# MainBoard.net
KiCad netlist of a schematic drawn in Altium Designer
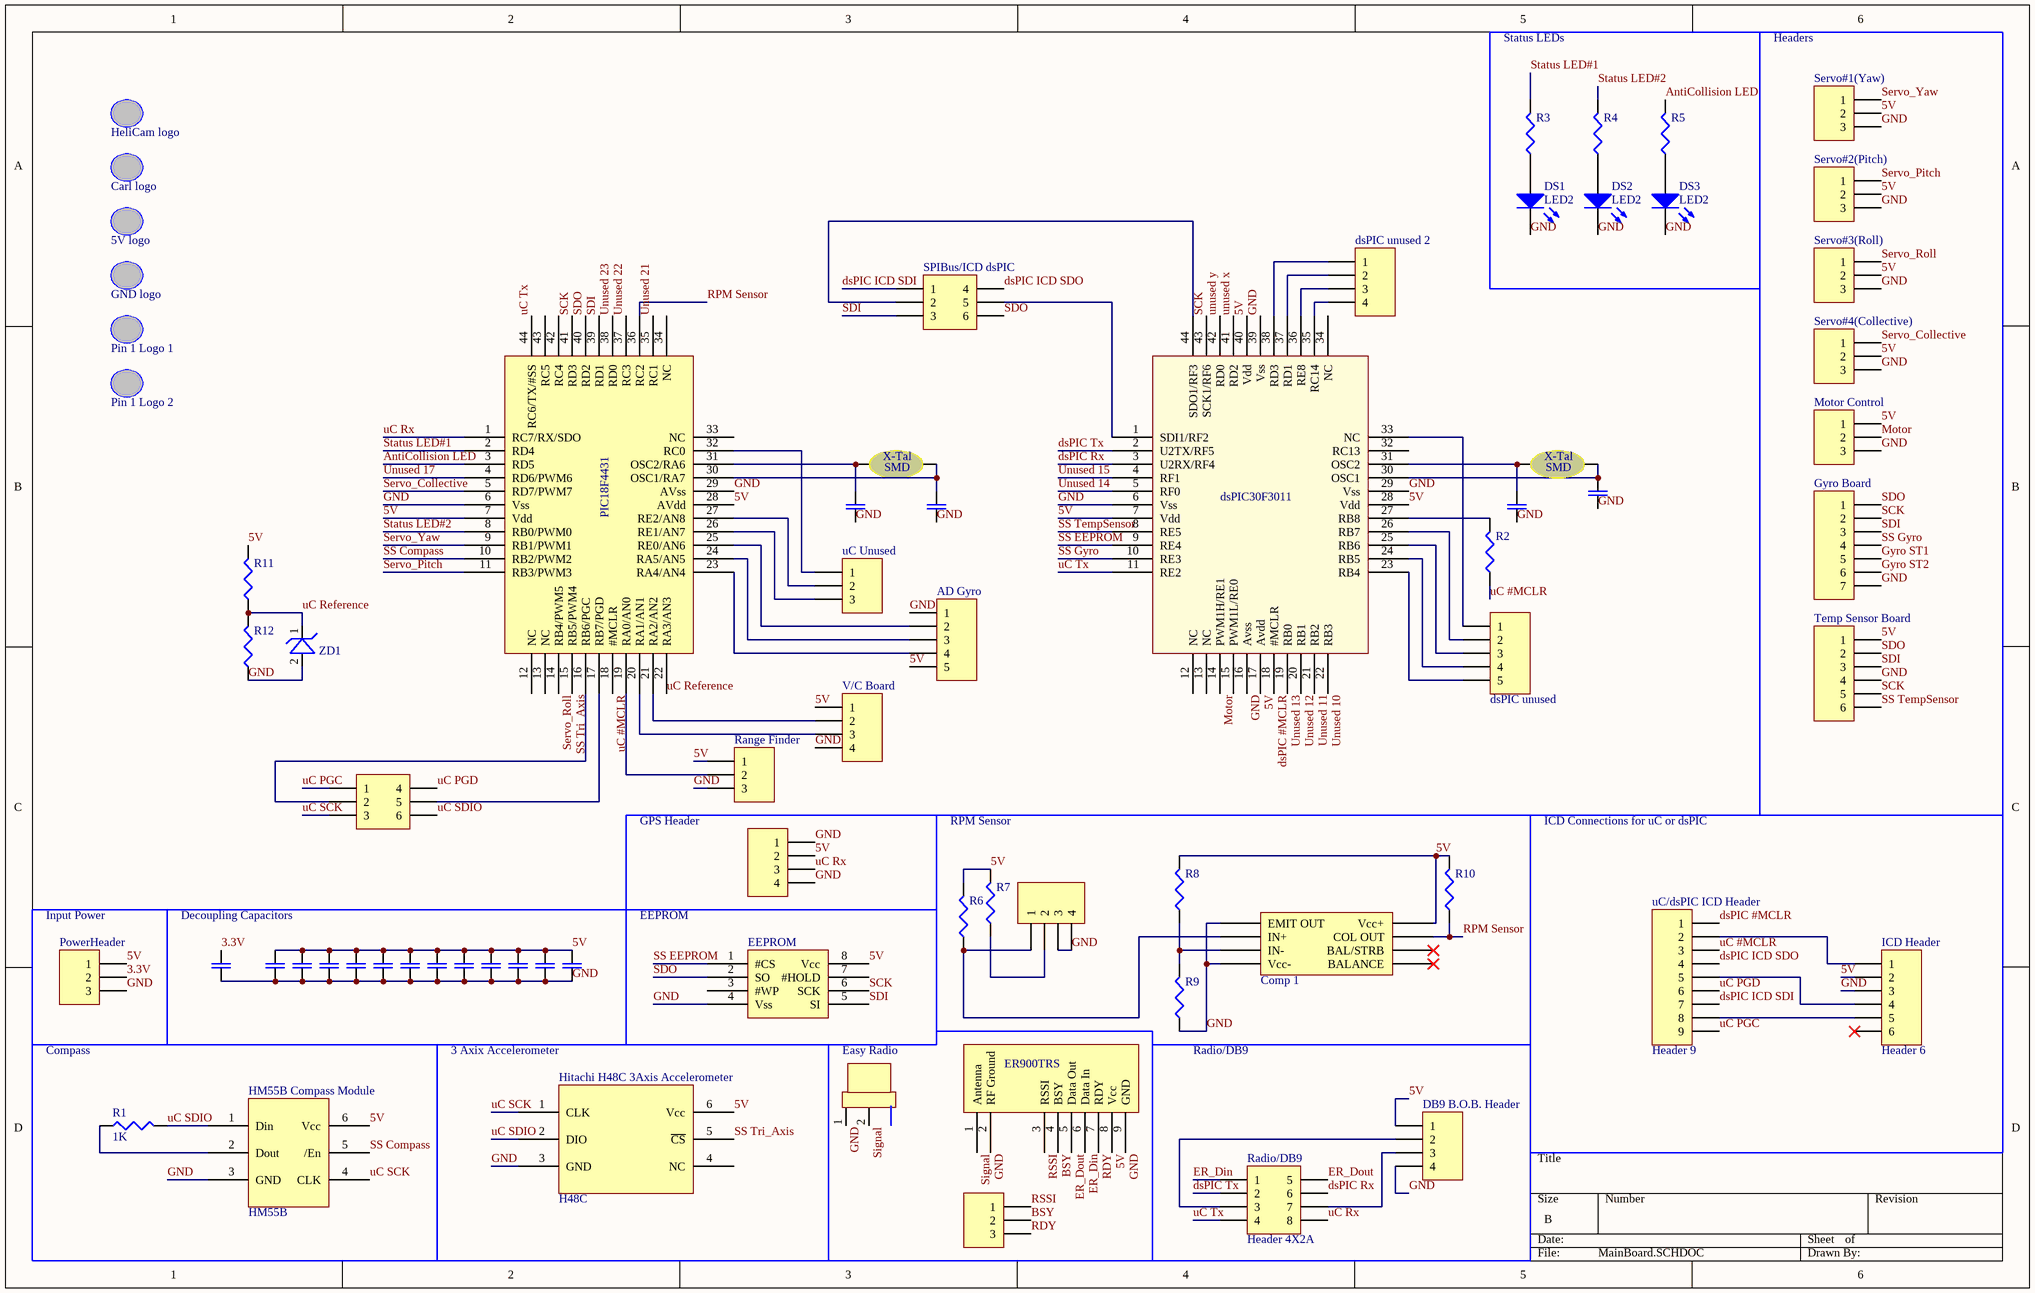
[diagram p0: MainBoard.SCHDOC]

(export (version "E")
  (design (tool "Eeschema 10.0.6"))
  (components
    (comp (ref "5V logo") (value "logo") (footprint "5V logo") (libsource (lib "MyParts") (part "logo")))
    (comp (ref "AD Gyro")
      (value "Header 5")
      (footprint "HDR1X5")
      (description "Header, 5-Pin")
      (fields (field (name "PUBLISHER") "Altium Limited"))
      (libsource (lib "Miscellaneous Connectors") (part "Header 5"))
    )
    (comp (ref "Antenna Connector 1")
      (value "Antenna Connector")
      (footprint "Antenna Connector")
      (libsource (lib "MyParts") (part "Antenna Connector"))
    )
    (comp (ref "Carl logo") (value "logo") (footprint "Carl Logo") (libsource (lib "MyParts") (part "logo")))
    (comp (ref "Comp 1")
      (value "Comparator")
      (footprint "8-Pin DIP")
      (libsource (lib "MyParts") (part "LP311P"))
    )
    (comp (ref "DB9 B.O.B. Header")
      (value "DB9 Break Out Board Header")
      (footprint "HDR1X4")
      (description "Header, 4-Pin")
      (fields (field (name "PUBLISHER") "Altium Limited"))
      (libsource (lib "Miscellaneous Connectors") (part "Header 4"))
    )
    (comp (ref "DS1")
      (value "LED2")
      (footprint "DSO-F2/D6.1")
      (description "Typical RED, GREEN, YELLOW, AMBER GaAs LED")
      (fields (field (name "PUBLISHER") "Altium Limited"))
      (libsource (lib "Miscellaneous Devices") (part "LED2"))
    )
    (comp (ref "DS2")
      (value "LED2")
      (footprint "DSO-F2/D6.1")
      (description "Typical RED, GREEN, YELLOW, AMBER GaAs LED")
      (fields (field (name "PUBLISHER") "Altium Limited"))
      (libsource (lib "Miscellaneous Devices") (part "LED2"))
    )
    (comp (ref "DS3")
      (value "LED2")
      (footprint "DSO-F2/D6.1")
      (description "Typical RED, GREEN, YELLOW, AMBER GaAs LED")
      (fields (field (name "PUBLISHER") "Altium Limited"))
      (libsource (lib "Miscellaneous Devices") (part "LED2"))
    )
    (comp (ref "dsPIC unused")
      (value "Header 5")
      (footprint "HDR1X5")
      (description "Header, 5-Pin")
      (fields (field (name "PUBLISHER") "Altium Limited"))
      (libsource (lib "Miscellaneous Connectors") (part "Header 5"))
    )
    (comp (ref "dsPIC unused 2")
      (value "Header 4")
      (footprint "HDR1X4")
      (description "Header, 4-Pin")
      (fields (field (name "PUBLISHER") "Altium Limited"))
      (libsource (lib "Miscellaneous Connectors") (part "Header 4"))
    )
    (comp (ref "dsPIC30F3011")
      (value "dsPIC30F3011")
      (footprint "QFP7x7-G32/N")
      (libsource (lib "dsPIC30F3011") (part "dsPIC30F3011"))
    )
    (comp (ref "EEPROM")
      (value "25LC256 EEPROM")
      (footprint "EEPROM")
      (libsource (lib "EEPROM") (part "EEPROM"))
    )
    (comp (ref "ER900TRS")
      (value "Easy Radio 900MHz")
      (footprint "ER900TRS")
      (libsource (lib "ER900TRS") (part "ER900TRS"))
    )
    (comp (ref "GND logo") (value "logo") (footprint "GND logo") (libsource (lib "MyParts") (part "logo")))
    (comp (ref "GPS Header")
      (value "GPS Header")
      (footprint "HDR1X4")
      (description "Header, 4-Pin")
      (fields (field (name "PUBLISHER") "Altium Limited"))
      (libsource (lib "") (part "Header 4_1"))
    )
    (comp (ref "Gyro Board")
      (value "Header for Gyro Board")
      (footprint "HDR1X7")
      (description "Header, 7-Pin")
      (fields (field (name "PUBLISHER") "Altium Limited"))
      (libsource (lib "Miscellaneous Connectors") (part "Header 7"))
    )
    (comp (ref "H48C")
      (value "Hitachi H48C 3Axis Accelerometer")
      (footprint "H48C")
      (description "3 Axis Accelerometer")
      (libsource (lib "H48C") (part "H48C"))
    )
    (comp (ref "HeliCam logo")
      (value "logo")
      (footprint "HeliCamosun")
      (libsource (lib "MyParts") (part "logo"))
    )
    (comp (ref "HM55B")
      (value "HM55B Compass Module")
      (footprint "HM55B")
      (libsource (lib "HM55B") (part "HM55B Compass Module"))
    )
    (comp (ref "ICD Header")
      (value "Header 6")
      (footprint "HDR1X6")
      (description "Header, 6-Pin")
      (fields (field (name "PUBLISHER") "Altium Limited"))
      (libsource (lib "Miscellaneous Connectors") (part "Header 6"))
    )
    (comp (ref "Motor Control")
      (value "Connector for Motor Control")
      (footprint "HDR1X3")
      (description "Header, 3-Pin")
      (fields (field (name "PUBLISHER") "Altium Limited"))
      (libsource (lib "") (part "Header 3_1"))
    )
    (comp (ref "PIC18F4431")
      (value "PIC18F4431")
      (footprint "QFP7x7-G32/N")
      (libsource (lib "PIC18F4431") (part "PIC18F4431"))
    )
    (comp (ref "Pin 1 Logo 1")
      (value "logo")
      (footprint "Pin 1 Logo")
      (libsource (lib "MyParts") (part "logo"))
    )
    (comp (ref "Pin 1 Logo 2")
      (value "logo")
      (footprint "Pin 1 Logo")
      (libsource (lib "MyParts") (part "logo"))
    )
    (comp (ref "PowerHeader")
      (value "Header 3")
      (footprint "HDR1X3")
      (description "Header, 3-Pin")
      (fields (field (name "PUBLISHER") "Altium Limited"))
      (libsource (lib "") (part "Header 3_1"))
    )
    (comp (ref "R1")
      (value "1K")
      (footprint "CR1608-0603")
      (description "Resistor")
      (fields (field (name "PUBLISHER") "Altium Limited"))
      (libsource (lib "Miscellaneous Devices") (part "Res3"))
    )
    (comp (ref "R2")
      (value "Res3")
      (footprint "CR1608-0603")
      (description "Resistor")
      (fields (field (name "PUBLISHER") "Altium Limited"))
      (libsource (lib "Miscellaneous Devices") (part "Res3"))
    )
    (comp (ref "R3")
      (value "Res3")
      (footprint "CR1608-0603")
      (description "Resistor")
      (fields (field (name "PUBLISHER") "Altium Limited"))
      (libsource (lib "Miscellaneous Devices") (part "Res3"))
    )
    (comp (ref "R4")
      (value "Res3")
      (footprint "CR1608-0603")
      (description "Resistor")
      (fields (field (name "PUBLISHER") "Altium Limited"))
      (libsource (lib "Miscellaneous Devices") (part "Res3"))
    )
    (comp (ref "R5")
      (value "Res3")
      (footprint "CR1608-0603")
      (description "Resistor")
      (fields (field (name "PUBLISHER") "Altium Limited"))
      (libsource (lib "Miscellaneous Devices") (part "Res3"))
    )
    (comp (ref "R6")
      (value "Res3")
      (footprint "CR1608-0603")
      (description "Resistor")
      (fields (field (name "PUBLISHER") "Altium Limited"))
      (libsource (lib "Miscellaneous Devices") (part "Res3"))
    )
    (comp (ref "R7")
      (value "Res3")
      (footprint "CR1608-0603")
      (description "Resistor")
      (fields (field (name "PUBLISHER") "Altium Limited"))
      (libsource (lib "Miscellaneous Devices") (part "Res3"))
    )
    (comp (ref "R8")
      (value "Res3")
      (footprint "CR1608-0603")
      (description "Resistor")
      (fields (field (name "PUBLISHER") "Altium Limited"))
      (libsource (lib "Miscellaneous Devices") (part "Res3"))
    )
    (comp (ref "R9")
      (value "Res3")
      (footprint "CR1608-0603")
      (description "Resistor")
      (fields (field (name "PUBLISHER") "Altium Limited"))
      (libsource (lib "Miscellaneous Devices") (part "Res3"))
    )
    (comp (ref "R10")
      (value "Res3")
      (footprint "CR1608-0603")
      (description "Resistor")
      (fields (field (name "PUBLISHER") "Altium Limited"))
      (libsource (lib "Miscellaneous Devices") (part "Res3"))
    )
    (comp (ref "R11")
      (value "Res3")
      (footprint "CR1608-0603")
      (description "Resistor")
      (fields (field (name "PUBLISHER") "Altium Limited"))
      (libsource (lib "Miscellaneous Devices") (part "Res3"))
    )
    (comp (ref "R12")
      (value "Res3")
      (footprint "CR1608-0603")
      (description "Resistor")
      (fields (field (name "PUBLISHER") "Altium Limited"))
      (libsource (lib "Miscellaneous Devices") (part "Res3"))
    )
    (comp (ref "Radio Header")
      (value "Extra Radio Pins")
      (footprint "HDR1X3")
      (description "Header, 3-Pin")
      (fields (field (name "PUBLISHER") "Altium Limited"))
      (libsource (lib "") (part "Header 3_1"))
    )
    (comp (ref "Radio/DB9")
      (value "Header 4X2A")
      (footprint "HDR2X4_CEN")
      (description "Header, 4-Pin, Dual row")
      (fields (field (name "PUBLISHER") "Altium Limited"))
      (libsource (lib "Miscellaneous Connectors") (part "Header 4X2A"))
    )
    (comp (ref "Range Finder")
      (value "Header 3")
      (footprint "HDR1X3")
      (description "Header, 3-Pin")
      (fields (field (name "PUBLISHER") "Altium Limited"))
      (libsource (lib "Miscellaneous Connectors") (part "Header 3"))
    )
    (comp (ref "Servo#1(Yaw)")
      (value "Connector for Servo Motor")
      (footprint "HDR1X3")
      (description "Header, 3-Pin")
      (fields (field (name "PUBLISHER") "Altium Limited"))
      (libsource (lib "") (part "Header 3_1"))
    )
    (comp (ref "Servo#2(Pitch)")
      (value "Connector for Servo Motor")
      (footprint "HDR1X3")
      (description "Header, 3-Pin")
      (fields (field (name "PUBLISHER") "Altium Limited"))
      (libsource (lib "") (part "Header 3_1"))
    )
    (comp (ref "Servo#3(Roll)")
      (value "Connector for Servo Motor")
      (footprint "HDR1X3")
      (description "Header, 3-Pin")
      (fields (field (name "PUBLISHER") "Altium Limited"))
      (libsource (lib "") (part "Header 3_1"))
    )
    (comp (ref "Servo#4(Collective)")
      (value "Connector for Servo Motor")
      (footprint "HDR1X3")
      (description "Header, 3-Pin")
      (fields (field (name "PUBLISHER") "Altium Limited"))
      (libsource (lib "") (part "Header 3_1"))
    )
    (comp (ref "SMD 1206 1")
      (value "SMD 1206")
      (footprint "SMD 1206")
      (description "SMD 1206 Package Type")
      (libsource (lib "MyParts") (part "SMD 1206"))
    )
    (comp (ref "SMD 1206 2")
      (value "SMD 1206")
      (footprint "SMD 1206")
      (description "SMD 1206 Package Type")
      (libsource (lib "MyParts") (part "SMD 1206"))
    )
    (comp (ref "SMD 1206 3")
      (value "SMD 1206")
      (footprint "SMD 1206")
      (description "SMD 1206 Package Type")
      (libsource (lib "MyParts") (part "SMD 1206"))
    )
    (comp (ref "SMD 1206 4")
      (value "SMD 1206")
      (footprint "SMD 1206")
      (description "SMD 1206 Package Type")
      (libsource (lib "MyParts") (part "SMD 1206"))
    )
    (comp (ref "SMD 1206 5")
      (value "SMD 1206")
      (footprint "SMD 1206")
      (description "SMD 1206 Package Type")
      (libsource (lib "MyParts") (part "SMD 1206"))
    )
    (comp (ref "SMD 1206 6")
      (value "SMD 1206")
      (footprint "SMD 1206")
      (description "SMD 1206 Package Type")
      (libsource (lib "MyParts") (part "SMD 1206"))
    )
    (comp (ref "SMD 1206 7")
      (value "SMD 1206")
      (footprint "SMD 1206")
      (description "SMD 1206 Package Type")
      (libsource (lib "MyParts") (part "SMD 1206"))
    )
    (comp (ref "SMD 1206 8")
      (value "SMD 1206")
      (footprint "SMD 1206")
      (description "SMD 1206 Package Type")
      (libsource (lib "MyParts") (part "SMD 1206"))
    )
    (comp (ref "SMD 1206 9")
      (value "SMD 1206")
      (footprint "SMD 1206")
      (description "SMD 1206 Package Type")
      (libsource (lib "MyParts") (part "SMD 1206"))
    )
    (comp (ref "SMD 1206 10")
      (value "SMD 1206")
      (footprint "SMD 1206")
      (description "SMD 1206 Package Type")
      (libsource (lib "MyParts") (part "SMD 1206"))
    )
    (comp (ref "SMD 1206 11")
      (value "SMD 1206")
      (footprint "SMD 1206")
      (description "SMD 1206 Package Type")
      (libsource (lib "MyParts") (part "SMD 1206"))
    )
    (comp (ref "SMD 1206 12")
      (value "SMD 1206")
      (footprint "SMD 1206")
      (description "SMD 1206 Package Type")
      (libsource (lib "MyParts") (part "SMD 1206"))
    )
    (comp (ref "SMD 1206 13")
      (value "SMD 1206")
      (footprint "SMD 1206")
      (description "SMD 1206 Package Type")
      (libsource (lib "MyParts") (part "SMD 1206"))
    )
    (comp (ref "SMD 1206 14")
      (value "SMD 1206")
      (footprint "SMD 1206")
      (description "SMD 1206 Package Type")
      (libsource (lib "MyParts") (part "SMD 1206"))
    )
    (comp (ref "SMD 1206 15")
      (value "SMD 1206")
      (footprint "SMD 1206")
      (description "SMD 1206 Package Type")
      (libsource (lib "MyParts") (part "SMD 1206"))
    )
    (comp (ref "SMD 1206 16")
      (value "SMD 1206")
      (footprint "SMD 1206")
      (description "SMD 1206 Package Type")
      (libsource (lib "MyParts") (part "SMD 1206"))
    )
    (comp (ref "SMD 1206 17")
      (value "SMD 1206")
      (footprint "SMD 1206")
      (description "SMD 1206 Package Type")
      (libsource (lib "MyParts") (part "SMD 1206"))
    )
    (comp (ref "SMD X-Tal 1")
      (value "SMD X-Tal")
      (footprint "SMD X-Tal")
      (libsource (lib "MyParts") (part "SMD X-Tal"))
    )
    (comp (ref "SMD X-Tal 2")
      (value "SMD X-Tal")
      (footprint "SMD X-Tal")
      (libsource (lib "MyParts") (part "SMD X-Tal"))
    )
    (comp (ref "SPIBus/ICD")
      (value "Header 3X2A")
      (footprint "HDR2X3_CEN")
      (description "Header, 3-Pin, Dual row")
      (fields (field (name "PUBLISHER") "Altium Limited"))
      (libsource (lib "Miscellaneous Connectors") (part "Header 3X2A"))
    )
    (comp (ref "SPIBus/ICD dsPIC")
      (value "Header 3X2A")
      (footprint "HDR2X3_CEN")
      (description "Header, 3-Pin, Dual row")
      (fields (field (name "PUBLISHER") "Altium Limited"))
      (libsource (lib "Miscellaneous Connectors") (part "Header 3X2A"))
    )
    (comp (ref "Stef's Connector")
      (value "Header 4")
      (footprint "HDR1X4")
      (description "Header, 4-Pin")
      (fields (field (name "PUBLISHER") "Altium Limited"))
      (libsource (lib "") (part "Header 4_2"))
    )
    (comp (ref "Temp Sensor Board")
      (value "SPI Temp Sensor Header")
      (footprint "HDR1X6")
      (description "Header, 6-Pin")
      (fields (field (name "PUBLISHER") "Altium Limited"))
      (libsource (lib "") (part "Header 6_1"))
    )
    (comp (ref "uC Unused")
      (value "Header 3")
      (footprint "HDR1X3")
      (description "Header, 3-Pin")
      (fields (field (name "PUBLISHER") "Altium Limited"))
      (libsource (lib "Miscellaneous Connectors") (part "Header 3"))
    )
    (comp (ref "uC/dsPIC ICD Header")
      (value "Header 9")
      (footprint "HDR1X9")
      (description "uC/dsPIC ICD Header")
      (fields (field (name "PUBLISHER") "Altium Limited"))
      (libsource (lib "Miscellaneous Connectors") (part "Header 9"))
    )
    (comp (ref "V/C Board")
      (value "Voltage/Current Board Header")
      (footprint "HDR1X4")
      (description "Header, 4-Pin")
      (fields (field (name "PUBLISHER") "Altium Limited"))
      (libsource (lib "Miscellaneous Connectors") (part "Header 4"))
    )
    (comp (ref "ZD1")
      (value "CZRF52C3")
      (footprint "Zener Diode")
      (libsource (lib "MyParts") (part "CZRF52C3"))
    )
  )
  (nets
    (net (code "1") (name "/3.3V") (class "Default")
      (node (ref "PowerHeader") (pin "2") (pinfunction "2_2") (pintype "passive"))
      (node (ref "SMD 1206 10") (pin "1") (pinfunction "1_1") (pintype "passive"))
    )
    (net (code "2") (name "/5V") (class "Default")
      (node (ref "AD Gyro") (pin "5") (pinfunction "5_5") (pintype "passive"))
      (node (ref "Comp 1") (pin "8") (pinfunction "Vcc+_8") (pintype "passive"))
      (node (ref "DB9 B.O.B. Header") (pin "1") (pinfunction "1_1") (pintype "passive"))
      (node (ref "EEPROM") (pin "8") (pinfunction "Vcc_8") (pintype "passive"))
      (node (ref "ER900TRS") (pin "8") (pinfunction "Vcc_8") (pintype "passive"))
      (node (ref "GPS Header") (pin "2") (pinfunction "2_2") (pintype "passive"))
      (node (ref "H48C") (pin "6") (pinfunction "Vcc_6") (pintype "passive"))
      (node (ref "HM55B") (pin "6") (pinfunction "Vcc_6") (pintype "passive"))
      (node (ref "ICD Header") (pin "2") (pinfunction "2_2") (pintype "passive"))
      (node (ref "Motor Control") (pin "1") (pinfunction "1_1") (pintype "passive"))
      (node (ref "PIC18F4431") (pin "28") (pinfunction "AVdd_28") (pintype "passive"))
      (node (ref "PIC18F4431") (pin "7") (pinfunction "Vdd_7") (pintype "passive"))
      (node (ref "PowerHeader") (pin "1") (pinfunction "1_1") (pintype "passive"))
      (node (ref "R10") (pin "2") (pinfunction "2_2") (pintype "passive"))
      (node (ref "R11") (pin "2") (pinfunction "2_2") (pintype "passive"))
      (node (ref "R6") (pin "2") (pinfunction "2_2") (pintype "passive"))
      (node (ref "R7") (pin "2") (pinfunction "2_2") (pintype "passive"))
      (node (ref "R8") (pin "2") (pinfunction "2_2") (pintype "passive"))
      (node (ref "Range Finder") (pin "1") (pinfunction "1_1") (pintype "passive"))
      (node (ref "SMD 1206 1") (pin "1") (pinfunction "1_1") (pintype "passive"))
      (node (ref "SMD 1206 15") (pin "1") (pinfunction "1_1") (pintype "passive"))
      (node (ref "SMD 1206 16") (pin "1") (pinfunction "1_1") (pintype "passive"))
      (node (ref "SMD 1206 17") (pin "1") (pinfunction "1_1") (pintype "passive"))
      (node (ref "SMD 1206 2") (pin "1") (pinfunction "1_1") (pintype "passive"))
      (node (ref "SMD 1206 3") (pin "1") (pinfunction "1_1") (pintype "passive"))
      (node (ref "SMD 1206 4") (pin "1") (pinfunction "1_1") (pintype "passive"))
      (node (ref "SMD 1206 5") (pin "1") (pinfunction "1_1") (pintype "passive"))
      (node (ref "SMD 1206 6") (pin "1") (pinfunction "1_1") (pintype "passive"))
      (node (ref "SMD 1206 7") (pin "1") (pinfunction "1_1") (pintype "passive"))
      (node (ref "SMD 1206 8") (pin "1") (pinfunction "1_1") (pintype "passive"))
      (node (ref "SMD 1206 9") (pin "1") (pinfunction "1_1") (pintype "passive"))
      (node (ref "Servo#1(Yaw)") (pin "2") (pinfunction "2_2") (pintype "passive"))
      (node (ref "Servo#2(Pitch)") (pin "2") (pinfunction "2_2") (pintype "passive"))
      (node (ref "Servo#3(Roll)") (pin "2") (pinfunction "2_2") (pintype "passive"))
      (node (ref "Servo#4(Collective)") (pin "2") (pinfunction "2_2") (pintype "passive"))
      (node (ref "Temp Sensor Board") (pin "1") (pinfunction "1_1") (pintype "passive"))
      (node (ref "V/C Board") (pin "1") (pinfunction "1_1") (pintype "passive"))
      (node (ref "dsPIC30F3011") (pin "17") (pinfunction "Avdd_17") (pintype "passive"))
      (node (ref "dsPIC30F3011") (pin "28") (pinfunction "Vdd_28") (pintype "passive"))
      (node (ref "dsPIC30F3011") (pin "40") (pinfunction "Vdd_40") (pintype "passive"))
      (node (ref "dsPIC30F3011") (pin "7") (pinfunction "Vdd_7") (pintype "passive"))
    )
    (net (code "3") (name "/AntiCollision LED") (class "Default")
      (node (ref "PIC18F4431") (pin "3") (pinfunction "RD5_3") (pintype "passive"))
      (node (ref "R5") (pin "2") (pinfunction "2_2") (pintype "passive"))
    )
    (net (code "4") (name "/BSY") (class "Default")
      (node (ref "ER900TRS") (pin "4") (pinfunction "BSY_4") (pintype "passive"))
      (node (ref "Radio Header") (pin "2") (pinfunction "2_2") (pintype "passive"))
    )
    (net (code "5") (name "/ER_Din") (class "Default")
      (node (ref "ER900TRS") (pin "6") (pinfunction "Data_In_6") (pintype "passive"))
      (node (ref "Radio/DB9") (pin "1") (pinfunction "1_1") (pintype "passive"))
    )
    (net (code "6") (name "/ER_Dout") (class "Default")
      (node (ref "ER900TRS") (pin "5") (pinfunction "Data_Out_5") (pintype "passive"))
      (node (ref "Radio/DB9") (pin "5") (pinfunction "5_5") (pintype "passive"))
    )
    (net (code "7") (name "/GND") (class "Default")
      (node (ref "AD Gyro") (pin "1") (pinfunction "1_1") (pintype "passive"))
      (node (ref "Antenna Connector 1") (pin "1") (pinfunction "1_1") (pintype "passive"))
      (node (ref "Comp 1") (pin "1") (pinfunction "EMIT_OUT_1") (pintype "passive"))
      (node (ref "Comp 1") (pin "4") (pinfunction "Vcc-_4") (pintype "passive"))
      (node (ref "DB9 B.O.B. Header") (pin "4") (pinfunction "4_4") (pintype "passive"))
      (node (ref "DS1") (pin "2") (pinfunction "K_2") (pintype "passive"))
      (node (ref "DS2") (pin "2") (pinfunction "K_2") (pintype "passive"))
      (node (ref "DS3") (pin "2") (pinfunction "K_2") (pintype "passive"))
      (node (ref "EEPROM") (pin "4") (pinfunction "Vss_4") (pintype "passive"))
      (node (ref "ER900TRS") (pin "2") (pinfunction "RF_Ground_2") (pintype "passive"))
      (node (ref "ER900TRS") (pin "9") (pinfunction "GND_9") (pintype "passive"))
      (node (ref "GPS Header") (pin "1") (pinfunction "1_1") (pintype "passive"))
      (node (ref "GPS Header") (pin "4") (pinfunction "4_4") (pintype "passive"))
      (node (ref "Gyro Board") (pin "7") (pinfunction "7_7") (pintype "passive"))
      (node (ref "H48C") (pin "3") (pinfunction "GND_3") (pintype "passive"))
      (node (ref "HM55B") (pin "3") (pinfunction "GND_3") (pintype "passive"))
      (node (ref "ICD Header") (pin "3") (pinfunction "3_3") (pintype "passive"))
      (node (ref "Motor Control") (pin "3") (pinfunction "3_3") (pintype "passive"))
      (node (ref "PIC18F4431") (pin "29") (pinfunction "AVss_29") (pintype "passive"))
      (node (ref "PIC18F4431") (pin "6") (pinfunction "Vss_6") (pintype "passive"))
      (node (ref "PowerHeader") (pin "3") (pinfunction "3_3") (pintype "passive"))
      (node (ref "R12") (pin "1") (pinfunction "1_1") (pintype "passive"))
      (node (ref "R9") (pin "1") (pinfunction "1_1") (pintype "passive"))
      (node (ref "Range Finder") (pin "3") (pinfunction "3_3") (pintype "passive"))
      (node (ref "SMD 1206 1") (pin "2") (pinfunction "2_2") (pintype "passive"))
      (node (ref "SMD 1206 10") (pin "2") (pinfunction "2_2") (pintype "passive"))
      (node (ref "SMD 1206 11") (pin "2") (pinfunction "2_2") (pintype "passive"))
      (node (ref "SMD 1206 12") (pin "2") (pinfunction "2_2") (pintype "passive"))
      (node (ref "SMD 1206 13") (pin "2") (pinfunction "2_2") (pintype "passive"))
      (node (ref "SMD 1206 14") (pin "2") (pinfunction "2_2") (pintype "passive"))
      (node (ref "SMD 1206 15") (pin "2") (pinfunction "2_2") (pintype "passive"))
      (node (ref "SMD 1206 16") (pin "2") (pinfunction "2_2") (pintype "passive"))
      (node (ref "SMD 1206 17") (pin "2") (pinfunction "2_2") (pintype "passive"))
      (node (ref "SMD 1206 2") (pin "2") (pinfunction "2_2") (pintype "passive"))
      (node (ref "SMD 1206 3") (pin "2") (pinfunction "2_2") (pintype "passive"))
      (node (ref "SMD 1206 4") (pin "2") (pinfunction "2_2") (pintype "passive"))
      (node (ref "SMD 1206 5") (pin "2") (pinfunction "2_2") (pintype "passive"))
      (node (ref "SMD 1206 6") (pin "2") (pinfunction "2_2") (pintype "passive"))
      (node (ref "SMD 1206 7") (pin "2") (pinfunction "2_2") (pintype "passive"))
      (node (ref "SMD 1206 8") (pin "2") (pinfunction "2_2") (pintype "passive"))
      (node (ref "SMD 1206 9") (pin "2") (pinfunction "2_2") (pintype "passive"))
      (node (ref "Servo#1(Yaw)") (pin "3") (pinfunction "3_3") (pintype "passive"))
      (node (ref "Servo#2(Pitch)") (pin "3") (pinfunction "3_3") (pintype "passive"))
      (node (ref "Servo#3(Roll)") (pin "3") (pinfunction "3_3") (pintype "passive"))
      (node (ref "Servo#4(Collective)") (pin "3") (pinfunction "3_3") (pintype "passive"))
      (node (ref "Stef's Connector") (pin "3") (pinfunction "3_3") (pintype "passive"))
      (node (ref "Stef's Connector") (pin "4") (pinfunction "4_4") (pintype "passive"))
      (node (ref "Temp Sensor Board") (pin "4") (pinfunction "4_4") (pintype "passive"))
      (node (ref "V/C Board") (pin "4") (pinfunction "4_4") (pintype "passive"))
      (node (ref "ZD1") (pin "2") (pinfunction "2_2") (pintype "passive"))
      (node (ref "dsPIC30F3011") (pin "16") (pinfunction "Avss_16") (pintype "passive"))
      (node (ref "dsPIC30F3011") (pin "29") (pinfunction "Vss_29") (pintype "passive"))
      (node (ref "dsPIC30F3011") (pin "39") (pinfunction "Vss_39") (pintype "passive"))
      (node (ref "dsPIC30F3011") (pin "6") (pinfunction "Vss_6") (pintype "passive"))
    )
    (net (code "8") (name "/Gyro ST1") (class "Default")
      (node (ref "Gyro Board") (pin "5") (pinfunction "5_5") (pintype "passive"))
    )
    (net (code "9") (name "/Gyro ST2") (class "Default")
      (node (ref "Gyro Board") (pin "6") (pinfunction "6_6") (pintype "passive"))
    )
    (net (code "10") (name "/Motor") (class "Default")
      (node (ref "Motor Control") (pin "2") (pinfunction "2_2") (pintype "passive"))
      (node (ref "dsPIC30F3011") (pin "14") (pinfunction "PWM1H/RE1_14") (pintype "passive"))
    )
    (net (code "11") (name "/RDY") (class "Default")
      (node (ref "ER900TRS") (pin "7") (pinfunction "RDY_7") (pintype "passive"))
      (node (ref "Radio Header") (pin "3") (pinfunction "3_3") (pintype "passive"))
    )
    (net (code "12") (name "/RPM Sensor") (class "Default")
      (node (ref "Comp 1") (pin "7") (pinfunction "COL_OUT_7") (pintype "passive"))
      (node (ref "PIC18F4431") (pin "36") (pinfunction "RC2_36") (pintype "passive"))
      (node (ref "R10") (pin "1") (pinfunction "1_1") (pintype "passive"))
    )
    (net (code "13") (name "/RSSI") (class "Default")
      (node (ref "ER900TRS") (pin "3") (pinfunction "RSSI_3") (pintype "passive"))
      (node (ref "Radio Header") (pin "1") (pinfunction "1_1") (pintype "passive"))
    )
    (net (code "14") (name "/SCK") (class "Default")
      (node (ref "EEPROM") (pin "6") (pinfunction "SCK_6") (pintype "passive"))
      (node (ref "Gyro Board") (pin "2") (pinfunction "2_2") (pintype "passive"))
      (node (ref "PIC18F4431") (pin "41") (pinfunction "RD3_41") (pintype "passive"))
      (node (ref "Temp Sensor Board") (pin "5") (pinfunction "5_5") (pintype "passive"))
      (node (ref "dsPIC30F3011") (pin "43") (pinfunction "SCK1/RF6_43") (pintype "passive"))
    )
    (net (code "15") (name "/SDI") (class "Default")
      (node (ref "EEPROM") (pin "5") (pinfunction "SI_5") (pintype "passive"))
      (node (ref "Gyro Board") (pin "3") (pinfunction "3_3") (pintype "passive"))
      (node (ref "PIC18F4431") (pin "39") (pinfunction "RD1_39") (pintype "passive"))
      (node (ref "SPIBus/ICD dsPIC") (pin "3") (pinfunction "3_3") (pintype "passive"))
      (node (ref "Temp Sensor Board") (pin "3") (pinfunction "3_3") (pintype "passive"))
    )
    (net (code "16") (name "/SDO") (class "Default")
      (node (ref "EEPROM") (pin "2") (pinfunction "SO_2") (pintype "passive"))
      (node (ref "Gyro Board") (pin "1") (pinfunction "1_1") (pintype "passive"))
      (node (ref "PIC18F4431") (pin "40") (pinfunction "RD2_40") (pintype "passive"))
      (node (ref "SPIBus/ICD dsPIC") (pin "6") (pinfunction "6_6") (pintype "passive"))
      (node (ref "Temp Sensor Board") (pin "2") (pinfunction "2_2") (pintype "passive"))
    )
    (net (code "17") (name "/SS Compass") (class "Default")
      (node (ref "HM55B") (pin "5") (pinfunction "/En_5") (pintype "passive"))
      (node (ref "PIC18F4431") (pin "10") (pinfunction "RB2/PWM2_10") (pintype "passive"))
    )
    (net (code "18") (name "/SS EEPROM") (class "Default")
      (node (ref "EEPROM") (pin "1") (pinfunction "#CS_1") (pintype "passive"))
      (node (ref "dsPIC30F3011") (pin "9") (pinfunction "RE4_9") (pintype "passive"))
    )
    (net (code "19") (name "/SS Gyro") (class "Default")
      (node (ref "Gyro Board") (pin "4") (pinfunction "4_4") (pintype "passive"))
      (node (ref "dsPIC30F3011") (pin "10") (pinfunction "RE3_10") (pintype "passive"))
    )
    (net (code "20") (name "/SS TempSensor") (class "Default")
      (node (ref "Temp Sensor Board") (pin "6") (pinfunction "6_6") (pintype "passive"))
      (node (ref "dsPIC30F3011") (pin "8") (pinfunction "RE5_8") (pintype "passive"))
    )
    (net (code "21") (name "/SS Tri_Axis") (class "Default")
      (node (ref "H48C") (pin "5") (pinfunction "~{CS}_5") (pintype "passive"))
      (node (ref "PIC18F4431") (pin "15") (pinfunction "RB5/PWM4_15") (pintype "passive"))
    )
    (net (code "22") (name "/Servo_Collective") (class "Default")
      (node (ref "PIC18F4431") (pin "5") (pinfunction "RD7/PWM7_5") (pintype "passive"))
      (node (ref "Servo#4(Collective)") (pin "1") (pinfunction "1_1") (pintype "passive"))
    )
    (net (code "23") (name "/Servo_Pitch") (class "Default")
      (node (ref "PIC18F4431") (pin "11") (pinfunction "RB3/PWM3_11") (pintype "passive"))
      (node (ref "Servo#2(Pitch)") (pin "1") (pinfunction "1_1") (pintype "passive"))
    )
    (net (code "24") (name "/Servo_Roll") (class "Default")
      (node (ref "PIC18F4431") (pin "14") (pinfunction "RB4/PWM5_14") (pintype "passive"))
      (node (ref "Servo#3(Roll)") (pin "1") (pinfunction "1_1") (pintype "passive"))
    )
    (net (code "25") (name "/Servo_Yaw") (class "Default")
      (node (ref "PIC18F4431") (pin "9") (pinfunction "RB1/PWM1_9") (pintype "passive"))
      (node (ref "Servo#1(Yaw)") (pin "1") (pinfunction "1_1") (pintype "passive"))
    )
    (net (code "26") (name "/Signal") (class "Default")
      (node (ref "Antenna Connector 1") (pin "2") (pinfunction "2_2") (pintype "passive"))
      (node (ref "ER900TRS") (pin "1") (pinfunction "Antenna_1") (pintype "passive"))
    )
    (net (code "27") (name "/Status LED#1") (class "Default")
      (node (ref "PIC18F4431") (pin "2") (pinfunction "RD4_2") (pintype "passive"))
      (node (ref "R3") (pin "2") (pinfunction "2_2") (pintype "passive"))
    )
    (net (code "28") (name "/Status LED#2") (class "Default")
      (node (ref "PIC18F4431") (pin "8") (pinfunction "RB0/PWM0_8") (pintype "passive"))
      (node (ref "R4") (pin "2") (pinfunction "2_2") (pintype "passive"))
    )
    (net (code "29") (name "/Unused 10") (class "Default")
      (node (ref "dsPIC30F3011") (pin "22") (pinfunction "RB3_22") (pintype "passive"))
    )
    (net (code "30") (name "/Unused 11") (class "Default")
      (node (ref "dsPIC30F3011") (pin "21") (pinfunction "RB2_21") (pintype "passive"))
    )
    (net (code "31") (name "/Unused 12") (class "Default")
      (node (ref "dsPIC30F3011") (pin "20") (pinfunction "RB1_20") (pintype "passive"))
    )
    (net (code "32") (name "/Unused 13") (class "Default")
      (node (ref "dsPIC30F3011") (pin "19") (pinfunction "RB0_19") (pintype "passive"))
    )
    (net (code "33") (name "/Unused 14") (class "Default")
      (node (ref "dsPIC30F3011") (pin "5") (pinfunction "RF0_5") (pintype "passive"))
    )
    (net (code "34") (name "/Unused 15") (class "Default")
      (node (ref "dsPIC30F3011") (pin "4") (pinfunction "RF1_4") (pintype "passive"))
    )
    (net (code "35") (name "/Unused 17") (class "Default")
      (node (ref "PIC18F4431") (pin "4") (pinfunction "RD6/PWM6_4") (pintype "passive"))
    )
    (net (code "36") (name "/Unused 21") (class "Default")
      (node (ref "PIC18F4431") (pin "35") (pinfunction "RC1_35") (pintype "passive"))
    )
    (net (code "37") (name "/Unused 22") (class "Default")
      (node (ref "PIC18F4431") (pin "37") (pinfunction "RC3_37") (pintype "passive"))
    )
    (net (code "38") (name "/Unused 23") (class "Default")
      (node (ref "PIC18F4431") (pin "38") (pinfunction "RD0_38") (pintype "passive"))
    )
    (net (code "39") (name "/dsPIC #MCLR") (class "Default")
      (node (ref "dsPIC30F3011") (pin "18") (pinfunction "#MCLR_18") (pintype "passive"))
      (node (ref "uC/dsPIC ICD Header") (pin "1") (pinfunction "1_1") (pintype "passive"))
    )
    (net (code "40") (name "/dsPIC ICD SDI") (class "Default")
      (node (ref "SPIBus/ICD dsPIC") (pin "1") (pinfunction "1_1") (pintype "passive"))
      (node (ref "uC/dsPIC ICD Header") (pin "7") (pinfunction "7_7") (pintype "passive"))
    )
    (net (code "41") (name "/dsPIC ICD SDO") (class "Default")
      (node (ref "SPIBus/ICD dsPIC") (pin "4") (pinfunction "4_4") (pintype "passive"))
      (node (ref "uC/dsPIC ICD Header") (pin "4") (pinfunction "4_4") (pintype "passive"))
    )
    (net (code "42") (name "/dsPIC Rx") (class "Default")
      (node (ref "Radio/DB9") (pin "6") (pinfunction "6_6") (pintype "passive"))
      (node (ref "dsPIC30F3011") (pin "3") (pinfunction "U2RX/RF4_3") (pintype "passive"))
    )
    (net (code "43") (name "/dsPIC Tx") (class "Default")
      (node (ref "Radio/DB9") (pin "2") (pinfunction "2_2") (pintype "passive"))
      (node (ref "dsPIC30F3011") (pin "2") (pinfunction "U2TX/RF5_2") (pintype "passive"))
    )
    (net (code "44") (name "/uC #MCLR") (class "Default")
      (node (ref "PIC18F4431") (pin "18") (pinfunction "#MCLR_18") (pintype "passive"))
      (node (ref "R2") (pin "1") (pinfunction "1_1") (pintype "passive"))
      (node (ref "uC/dsPIC ICD Header") (pin "3") (pinfunction "3_3") (pintype "passive"))
    )
    (net (code "45") (name "/uC PGC") (class "Default")
      (node (ref "SPIBus/ICD") (pin "1") (pinfunction "1_1") (pintype "passive"))
      (node (ref "uC/dsPIC ICD Header") (pin "9") (pinfunction "9_9") (pintype "passive"))
    )
    (net (code "46") (name "/uC PGD") (class "Default")
      (node (ref "SPIBus/ICD") (pin "4") (pinfunction "4_4") (pintype "passive"))
      (node (ref "uC/dsPIC ICD Header") (pin "6") (pinfunction "6_6") (pintype "passive"))
    )
    (net (code "47") (name "/uC Reference") (class "Default")
      (node (ref "PIC18F4431") (pin "22") (pinfunction "RA3/AN3_22") (pintype "passive"))
      (node (ref "R11") (pin "1") (pinfunction "1_1") (pintype "passive"))
      (node (ref "R12") (pin "2") (pinfunction "2_2") (pintype "passive"))
      (node (ref "ZD1") (pin "1") (pinfunction "1_1") (pintype "passive"))
    )
    (net (code "48") (name "/uC Rx") (class "Default")
      (node (ref "GPS Header") (pin "3") (pinfunction "3_3") (pintype "passive"))
      (node (ref "PIC18F4431") (pin "1") (pinfunction "RC7/RX/SDO_1") (pintype "passive"))
      (node (ref "Radio/DB9") (pin "8") (pinfunction "8_8") (pintype "passive"))
    )
    (net (code "49") (name "/uC SCK") (class "Default")
      (node (ref "H48C") (pin "1") (pinfunction "CLK_1") (pintype "passive"))
      (node (ref "HM55B") (pin "4") (pinfunction "CLK_4") (pintype "passive"))
      (node (ref "SPIBus/ICD") (pin "3") (pinfunction "3_3") (pintype "passive"))
    )
    (net (code "50") (name "/uC SDIO") (class "Default")
      (node (ref "H48C") (pin "2") (pinfunction "DIO_2") (pintype "passive"))
      (node (ref "HM55B") (pin "1") (pinfunction "Din_1") (pintype "passive"))
      (node (ref "R1") (pin "2") (pinfunction "2_2") (pintype "passive"))
      (node (ref "SPIBus/ICD") (pin "6") (pinfunction "6_6") (pintype "passive"))
    )
    (net (code "51") (name "/uC Tx") (class "Default")
      (node (ref "PIC18F4431") (pin "44") (pinfunction "RC6/TX/#SS_44") (pintype "passive"))
      (node (ref "Radio/DB9") (pin "4") (pinfunction "4_4") (pintype "passive"))
      (node (ref "dsPIC30F3011") (pin "11") (pinfunction "RE2_11") (pintype "passive"))
    )
    (net (code "52") (name "/unused x") (class "Default")
      (node (ref "dsPIC30F3011") (pin "41") (pinfunction "RD2_41") (pintype "passive"))
    )
    (net (code "53") (name "/unused y") (class "Default")
      (node (ref "dsPIC30F3011") (pin "42") (pinfunction "RD0_42") (pintype "passive"))
    )
    (net (code "54") (name "Net-(Comp 1-IN+)") (class "Default")
      (node (ref "Comp 1") (pin "2") (pinfunction "IN+_2") (pintype "passive"))
      (node (ref "R6") (pin "1") (pinfunction "1_1") (pintype "passive"))
      (node (ref "Stef's Connector") (pin "1") (pinfunction "1_1") (pintype "passive"))
    )
    (net (code "55") (name "Net-(Comp 1-IN-)") (class "Default")
      (node (ref "Comp 1") (pin "3") (pinfunction "IN-_3") (pintype "passive"))
      (node (ref "R8") (pin "1") (pinfunction "1_1") (pintype "passive"))
      (node (ref "R9") (pin "2") (pinfunction "2_2") (pintype "passive"))
    )
    (net (code "56") (name "Net-(DB9 B.O.B. Header-Pad2)") (class "Default")
      (node (ref "DB9 B.O.B. Header") (pin "2") (pinfunction "2_2") (pintype "passive"))
      (node (ref "Radio/DB9") (pin "3") (pinfunction "3_3") (pintype "passive"))
    )
    (net (code "57") (name "Net-(DB9 B.O.B. Header-Pad3)") (class "Default")
      (node (ref "DB9 B.O.B. Header") (pin "3") (pinfunction "3_3") (pintype "passive"))
      (node (ref "Radio/DB9") (pin "7") (pinfunction "7_7") (pintype "passive"))
    )
    (net (code "58") (name "Net-(DS1-A)") (class "Default")
      (node (ref "DS1") (pin "1") (pinfunction "A_1") (pintype "passive"))
      (node (ref "R3") (pin "1") (pinfunction "1_1") (pintype "passive"))
    )
    (net (code "59") (name "Net-(DS2-A)") (class "Default")
      (node (ref "DS2") (pin "1") (pinfunction "A_1") (pintype "passive"))
      (node (ref "R4") (pin "1") (pinfunction "1_1") (pintype "passive"))
    )
    (net (code "60") (name "Net-(DS3-A)") (class "Default")
      (node (ref "DS3") (pin "1") (pinfunction "A_1") (pintype "passive"))
      (node (ref "R5") (pin "1") (pinfunction "1_1") (pintype "passive"))
    )
    (net (code "61") (name "Net-(HM55B-Dout)") (class "Default")
      (node (ref "HM55B") (pin "2") (pinfunction "Dout_2") (pintype "passive"))
      (node (ref "R1") (pin "1") (pinfunction "1_1") (pintype "passive"))
    )
    (net (code "62") (name "Net-(ICD Header-Pad1)") (class "Default")
      (node (ref "ICD Header") (pin "1") (pinfunction "1_1") (pintype "passive"))
      (node (ref "uC/dsPIC ICD Header") (pin "2") (pinfunction "2_2") (pintype "passive"))
    )
    (net (code "63") (name "Net-(ICD Header-Pad4)") (class "Default")
      (node (ref "ICD Header") (pin "4") (pinfunction "4_4") (pintype "passive"))
      (node (ref "uC/dsPIC ICD Header") (pin "5") (pinfunction "5_5") (pintype "passive"))
    )
    (net (code "64") (name "Net-(ICD Header-Pad5)") (class "Default")
      (node (ref "ICD Header") (pin "5") (pinfunction "5_5") (pintype "passive"))
      (node (ref "uC/dsPIC ICD Header") (pin "8") (pinfunction "8_8") (pintype "passive"))
    )
    (net (code "65") (name "Net-(PIC18F4431-OSC1{slash}RA7)") (class "Default")
      (node (ref "PIC18F4431") (pin "30") (pinfunction "OSC1/RA7_30") (pintype "passive"))
      (node (ref "SMD 1206 12") (pin "1") (pinfunction "1_1") (pintype "passive"))
      (node (ref "SMD X-Tal 1") (pin "2") (pinfunction "2_2") (pintype "passive"))
    )
    (net (code "66") (name "Net-(PIC18F4431-OSC2{slash}RA6)") (class "Default")
      (node (ref "PIC18F4431") (pin "31") (pinfunction "OSC2/RA6_31") (pintype "passive"))
      (node (ref "SMD 1206 11") (pin "1") (pinfunction "1_1") (pintype "passive"))
      (node (ref "SMD X-Tal 1") (pin "1") (pinfunction "1_1") (pintype "passive"))
    )
    (net (code "67") (name "Net-(PIC18F4431-RA0{slash}AN0)") (class "Default")
      (node (ref "PIC18F4431") (pin "19") (pinfunction "RA0/AN0_19") (pintype "passive"))
      (node (ref "Range Finder") (pin "2") (pinfunction "2_2") (pintype "passive"))
    )
    (net (code "68") (name "Net-(PIC18F4431-RA1{slash}AN1)") (class "Default")
      (node (ref "PIC18F4431") (pin "20") (pinfunction "RA1/AN1_20") (pintype "passive"))
      (node (ref "V/C Board") (pin "3") (pinfunction "3_3") (pintype "passive"))
    )
    (net (code "69") (name "Net-(PIC18F4431-RA2{slash}AN2)") (class "Default")
      (node (ref "PIC18F4431") (pin "21") (pinfunction "RA2/AN2_21") (pintype "passive"))
      (node (ref "V/C Board") (pin "2") (pinfunction "2_2") (pintype "passive"))
    )
    (net (code "70") (name "Net-(PIC18F4431-RA4{slash}AN4)") (class "Default")
      (node (ref "AD Gyro") (pin "4") (pinfunction "4_4") (pintype "passive"))
      (node (ref "PIC18F4431") (pin "23") (pinfunction "RA4/AN4_23") (pintype "passive"))
    )
    (net (code "71") (name "Net-(PIC18F4431-RA5{slash}AN5)") (class "Default")
      (node (ref "AD Gyro") (pin "3") (pinfunction "3_3") (pintype "passive"))
      (node (ref "PIC18F4431") (pin "24") (pinfunction "RA5/AN5_24") (pintype "passive"))
    )
    (net (code "72") (name "Net-(PIC18F4431-RB6{slash}PGC)") (class "Default")
      (node (ref "PIC18F4431") (pin "16") (pinfunction "RB6/PGC_16") (pintype "passive"))
      (node (ref "SPIBus/ICD") (pin "2") (pinfunction "2_2") (pintype "passive"))
    )
    (net (code "73") (name "Net-(PIC18F4431-RB7{slash}PGD)") (class "Default")
      (node (ref "PIC18F4431") (pin "17") (pinfunction "RB7/PGD_17") (pintype "passive"))
      (node (ref "SPIBus/ICD") (pin "5") (pinfunction "5_5") (pintype "passive"))
    )
    (net (code "74") (name "Net-(PIC18F4431-RC0)") (class "Default")
      (node (ref "PIC18F4431") (pin "32") (pinfunction "RC0_32") (pintype "passive"))
      (node (ref "uC Unused") (pin "1") (pinfunction "1_1") (pintype "passive"))
    )
    (net (code "75") (name "Net-(PIC18F4431-RE0{slash}AN6)") (class "Default")
      (node (ref "AD Gyro") (pin "2") (pinfunction "2_2") (pintype "passive"))
      (node (ref "PIC18F4431") (pin "25") (pinfunction "RE0/AN6_25") (pintype "passive"))
    )
    (net (code "76") (name "Net-(PIC18F4431-RE1{slash}AN7)") (class "Default")
      (node (ref "PIC18F4431") (pin "26") (pinfunction "RE1/AN7_26") (pintype "passive"))
      (node (ref "uC Unused") (pin "3") (pinfunction "3_3") (pintype "passive"))
    )
    (net (code "77") (name "Net-(PIC18F4431-RE2{slash}AN8)") (class "Default")
      (node (ref "PIC18F4431") (pin "27") (pinfunction "RE2/AN8_27") (pintype "passive"))
      (node (ref "uC Unused") (pin "2") (pinfunction "2_2") (pintype "passive"))
    )
    (net (code "78") (name "Net-(R7-Pad1)") (class "Default")
      (node (ref "R7") (pin "1") (pinfunction "1_1") (pintype "passive"))
      (node (ref "Stef's Connector") (pin "2") (pinfunction "2_2") (pintype "passive"))
    )
    (net (code "79") (name "Net-(dsPIC unused-Pad1)") (class "Default")
      (node (ref "dsPIC unused") (pin "1") (pinfunction "1_1") (pintype "passive"))
      (node (ref "dsPIC30F3011") (pin "33") (pinfunction "NC_33") (pintype "passive"))
    )
    (net (code "80") (name "Net-(dsPIC30F3011-OSC1)") (class "Default")
      (node (ref "SMD 1206 14") (pin "1") (pinfunction "1_1") (pintype "passive"))
      (node (ref "SMD X-Tal 2") (pin "2") (pinfunction "2_2") (pintype "passive"))
      (node (ref "dsPIC30F3011") (pin "30") (pinfunction "OSC1_30") (pintype "passive"))
    )
    (net (code "81") (name "Net-(dsPIC30F3011-OSC2)") (class "Default")
      (node (ref "SMD 1206 13") (pin "1") (pinfunction "1_1") (pintype "passive"))
      (node (ref "SMD X-Tal 2") (pin "1") (pinfunction "1_1") (pintype "passive"))
      (node (ref "dsPIC30F3011") (pin "31") (pinfunction "OSC2_31") (pintype "passive"))
    )
    (net (code "82") (name "Net-(dsPIC30F3011-RB4)") (class "Default")
      (node (ref "dsPIC unused") (pin "5") (pinfunction "5_5") (pintype "passive"))
      (node (ref "dsPIC30F3011") (pin "23") (pinfunction "RB4_23") (pintype "passive"))
    )
    (net (code "83") (name "Net-(dsPIC30F3011-RB5)") (class "Default")
      (node (ref "dsPIC unused") (pin "4") (pinfunction "4_4") (pintype "passive"))
      (node (ref "dsPIC30F3011") (pin "24") (pinfunction "RB5_24") (pintype "passive"))
    )
    (net (code "84") (name "Net-(dsPIC30F3011-RB6)") (class "Default")
      (node (ref "dsPIC unused") (pin "3") (pinfunction "3_3") (pintype "passive"))
      (node (ref "dsPIC30F3011") (pin "25") (pinfunction "RB6_25") (pintype "passive"))
    )
    (net (code "85") (name "Net-(dsPIC30F3011-RB7)") (class "Default")
      (node (ref "dsPIC unused") (pin "2") (pinfunction "2_2") (pintype "passive"))
      (node (ref "dsPIC30F3011") (pin "26") (pinfunction "RB7_26") (pintype "passive"))
    )
    (net (code "86") (name "Net-(dsPIC30F3011-RB8)") (class "Default")
      (node (ref "R2") (pin "2") (pinfunction "2_2") (pintype "passive"))
      (node (ref "dsPIC30F3011") (pin "27") (pinfunction "RB8_27") (pintype "passive"))
    )
    (net (code "87") (name "Net-(dsPIC30F3011-RC14)") (class "Default")
      (node (ref "dsPIC unused 2") (pin "4") (pinfunction "4_4") (pintype "passive"))
      (node (ref "dsPIC30F3011") (pin "35") (pinfunction "RC14_35") (pintype "passive"))
    )
    (net (code "88") (name "Net-(dsPIC30F3011-RD1)") (class "Default")
      (node (ref "dsPIC unused 2") (pin "2") (pinfunction "2_2") (pintype "passive"))
      (node (ref "dsPIC30F3011") (pin "37") (pinfunction "RD1_37") (pintype "passive"))
    )
    (net (code "89") (name "Net-(dsPIC30F3011-RD3)") (class "Default")
      (node (ref "dsPIC unused 2") (pin "1") (pinfunction "1_1") (pintype "passive"))
      (node (ref "dsPIC30F3011") (pin "38") (pinfunction "RD3_38") (pintype "passive"))
    )
    (net (code "90") (name "Net-(dsPIC30F3011-RE8)") (class "Default")
      (node (ref "dsPIC unused 2") (pin "3") (pinfunction "3_3") (pintype "passive"))
      (node (ref "dsPIC30F3011") (pin "36") (pinfunction "RE8_36") (pintype "passive"))
    )
    (net (code "91") (name "Net-(dsPIC30F3011-SDI1{slash}RF2)") (class "Default")
      (node (ref "SPIBus/ICD dsPIC") (pin "5") (pinfunction "5_5") (pintype "passive"))
      (node (ref "dsPIC30F3011") (pin "1") (pinfunction "SDI1/RF2_1") (pintype "passive"))
    )
    (net (code "92") (name "Net-(dsPIC30F3011-SDO1{slash}RF3)") (class "Default")
      (node (ref "SPIBus/ICD dsPIC") (pin "2") (pinfunction "2_2") (pintype "passive"))
      (node (ref "dsPIC30F3011") (pin "44") (pinfunction "SDO1/RF3_44") (pintype "passive"))
    )
    (net (code "93") (name "unconnected-(Comp 1-BALANCE-Pad5)") (class "Default")
      (node (ref "Comp 1") (pin "5") (pinfunction "BALANCE_5") (pintype "passive+no_connect"))
    )
    (net (code "94") (name "unconnected-(Comp 1-BAL{slash}STRB-Pad6)") (class "Default")
      (node (ref "Comp 1") (pin "6") (pinfunction "BAL/STRB_6") (pintype "passive+no_connect"))
    )
    (net (code "95") (name "unconnected-(EEPROM-#HOLD-Pad7)") (class "Default")
      (node (ref "EEPROM") (pin "7") (pinfunction "#HOLD_7") (pintype "passive"))
    )
    (net (code "96") (name "unconnected-(EEPROM-#WP-Pad3)") (class "Default")
      (node (ref "EEPROM") (pin "3") (pinfunction "#WP_3") (pintype "passive"))
    )
    (net (code "97") (name "unconnected-(H48C-NC-Pad4)") (class "Default")
      (node (ref "H48C") (pin "4") (pinfunction "NC_4") (pintype "passive"))
    )
    (net (code "98") (name "unconnected-(ICD Header-Pad6)") (class "Default")
      (node (ref "ICD Header") (pin "6") (pinfunction "6_6") (pintype "passive+no_connect"))
    )
    (net (code "99") (name "unconnected-(PIC18F4431-NC-Pad12)") (class "Default")
      (node (ref "PIC18F4431") (pin "12") (pinfunction "NC_12") (pintype "passive"))
    )
    (net (code "100") (name "unconnected-(PIC18F4431-NC-Pad13)") (class "Default")
      (node (ref "PIC18F4431") (pin "13") (pinfunction "NC_13") (pintype "passive"))
    )
    (net (code "101") (name "unconnected-(PIC18F4431-NC-Pad33)") (class "Default")
      (node (ref "PIC18F4431") (pin "33") (pinfunction "NC_33") (pintype "passive"))
    )
    (net (code "102") (name "unconnected-(PIC18F4431-NC-Pad34)") (class "Default")
      (node (ref "PIC18F4431") (pin "34") (pinfunction "NC_34") (pintype "passive"))
    )
    (net (code "103") (name "unconnected-(PIC18F4431-RC4-Pad42)") (class "Default")
      (node (ref "PIC18F4431") (pin "42") (pinfunction "RC4_42") (pintype "passive"))
    )
    (net (code "104") (name "unconnected-(PIC18F4431-RC5-Pad43)") (class "Default")
      (node (ref "PIC18F4431") (pin "43") (pinfunction "RC5_43") (pintype "passive"))
    )
    (net (code "105") (name "unconnected-(dsPIC30F3011-NC-Pad12)") (class "Default")
      (node (ref "dsPIC30F3011") (pin "12") (pinfunction "NC_12") (pintype "passive"))
    )
    (net (code "106") (name "unconnected-(dsPIC30F3011-NC-Pad13)") (class "Default")
      (node (ref "dsPIC30F3011") (pin "13") (pinfunction "NC_13") (pintype "passive"))
    )
    (net (code "107") (name "unconnected-(dsPIC30F3011-NC-Pad34)") (class "Default")
      (node (ref "dsPIC30F3011") (pin "34") (pinfunction "NC_34") (pintype "passive"))
    )
    (net (code "108") (name "unconnected-(dsPIC30F3011-PWM1L{slash}RE0-Pad15)") (class "Default")
      (node (ref "dsPIC30F3011") (pin "15") (pinfunction "PWM1L/RE0_15") (pintype "passive"))
    )
    (net (code "109") (name "unconnected-(dsPIC30F3011-RC13-Pad32)") (class "Default")
      (node (ref "dsPIC30F3011") (pin "32") (pinfunction "RC13_32") (pintype "passive"))
    )
  )
)
